# Grove_4-Digit_Display_V1_0.net
KiCad netlist of a schematic drawn in EAGLE
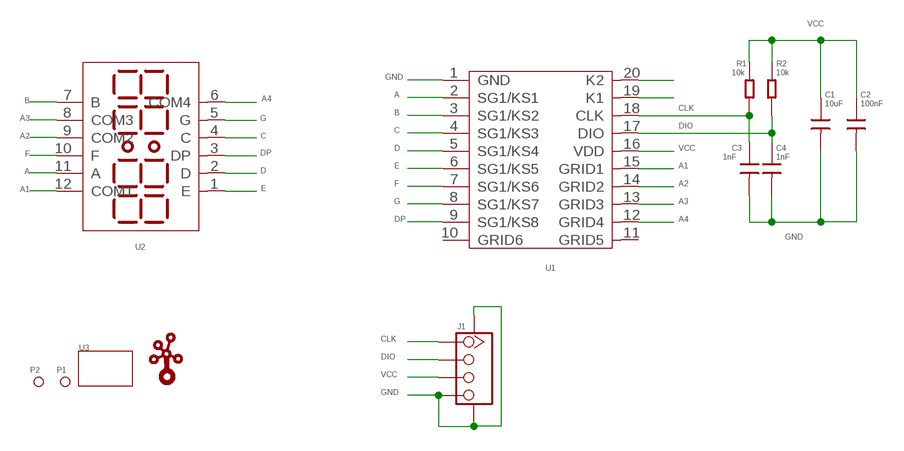
[diagram p0: schematic, sheet 1]

(export (version "E")
  (design (tool "Eeschema 10.0.6"))
  (components
    (comp (ref "C1")
      (value "10uF")
      (footprint "eagle-import:0603")
      (libsource (lib "eagle-import") (part "C-0603"))
    )
    (comp (ref "C2")
      (value "100nF")
      (footprint "eagle-import:0603")
      (libsource (lib "eagle-import") (part "C-0603"))
    )
    (comp (ref "C3")
      (value "1nF")
      (footprint "eagle-import:0603")
      (libsource (lib "eagle-import") (part "C-0603"))
    )
    (comp (ref "C4")
      (value "1nF")
      (footprint "eagle-import:0603")
      (libsource (lib "eagle-import") (part "C-0603"))
    )
    (comp (ref "J1")
      (value "TWIG-4P-2.0-SMD-FEMALE-REINFORCE'90D'")
      (footprint "eagle-import:4P-SMD-2.0-90D")
      (libsource (lib "eagle-import") (part "TWIG-4P-2.0-SMD-FEMALE-REINFORCE'90D'"))
    )
    (comp (ref "P1")
      (value "PAD-MARK")
      (footprint "eagle-import:ROUND-MARK-0.635")
      (libsource (lib "eagle-import") (part "PAD-MARK"))
    )
    (comp (ref "P2")
      (value "PAD-MARK")
      (footprint "eagle-import:ROUND-MARK-0.635")
      (libsource (lib "eagle-import") (part "PAD-MARK"))
    )
    (comp (ref "R1")
      (value "10k")
      (footprint "eagle-import:0603")
      (libsource (lib "eagle-import") (part "R-0603"))
    )
    (comp (ref "R2")
      (value "10k")
      (footprint "eagle-import:0603")
      (libsource (lib "eagle-import") (part "R-0603"))
    )
    (comp (ref "U$1")
      (value "LOGO-TWIGTWIGLOGO_SMALL")
      (footprint "eagle-import:TWIGLOGO_SMALL")
      (libsource (lib "eagle-import") (part "LOGO-TWIGTWIGLOGO_SMALL"))
    )
    (comp (ref "U1")
      (value "TM1637")
      (footprint "eagle-import:SOP20-10.45")
      (libsource (lib "eagle-import") (part "TM1637"))
    )
    (comp (ref "U2")
      (value "LED-4-BETY-7-SEG")
      (footprint "eagle-import:7-4-BYTE-SEG-2.54-30X14X7.3H")
      (libsource (lib "eagle-import") (part "LED-4-BETY-7-SEG"))
    )
    (comp (ref "U3")
      (value "TWIG-2U")
      (footprint "eagle-import:2U-DIM-W_-DRILL")
      (libsource (lib "eagle-import") (part "TWIG-2U"))
    )
  )
  (nets
    (net (code "1") (name "/A") (class "Default")
      (node (ref "U1") (pin "2") (pinfunction "SG1/KS1_2") (pintype "bidirectional"))
      (node (ref "U2") (pin "11") (pinfunction "A_11") (pintype "bidirectional"))
    )
    (net (code "2") (name "/A1") (class "Default")
      (node (ref "U1") (pin "15") (pinfunction "GRID1_15") (pintype "bidirectional"))
      (node (ref "U2") (pin "12") (pinfunction "COM1_12") (pintype "bidirectional"))
    )
    (net (code "3") (name "/A2") (class "Default")
      (node (ref "U1") (pin "14") (pinfunction "GRID2_14") (pintype "bidirectional"))
      (node (ref "U2") (pin "9") (pinfunction "COM2_9") (pintype "bidirectional"))
    )
    (net (code "4") (name "/A3") (class "Default")
      (node (ref "U1") (pin "13") (pinfunction "GRID3_13") (pintype "bidirectional"))
      (node (ref "U2") (pin "8") (pinfunction "COM3_8") (pintype "bidirectional"))
    )
    (net (code "5") (name "/A4") (class "Default")
      (node (ref "U1") (pin "12") (pinfunction "GRID4_12") (pintype "bidirectional"))
      (node (ref "U2") (pin "6") (pinfunction "COM4_6") (pintype "bidirectional"))
    )
    (net (code "6") (name "/B") (class "Default")
      (node (ref "U1") (pin "3") (pinfunction "SG1/KS2_3") (pintype "bidirectional"))
      (node (ref "U2") (pin "7") (pinfunction "B_7") (pintype "bidirectional"))
    )
    (net (code "7") (name "/C") (class "Default")
      (node (ref "U1") (pin "4") (pinfunction "SG1/KS3_4") (pintype "bidirectional"))
      (node (ref "U2") (pin "4") (pinfunction "C_4") (pintype "bidirectional"))
    )
    (net (code "8") (name "/CLK") (class "Default")
      (node (ref "C3") (pin "1") (pinfunction "1_1") (pintype "passive"))
      (node (ref "J1") (pin "1") (pinfunction "1_1") (pintype "bidirectional"))
      (node (ref "R1") (pin "2") (pinfunction "2_2") (pintype "passive"))
      (node (ref "U1") (pin "18") (pinfunction "CLK_18") (pintype "bidirectional"))
    )
    (net (code "9") (name "/D") (class "Default")
      (node (ref "U1") (pin "5") (pinfunction "SG1/KS4_5") (pintype "bidirectional"))
      (node (ref "U2") (pin "2") (pinfunction "D_2") (pintype "bidirectional"))
    )
    (net (code "10") (name "/DIO") (class "Default")
      (node (ref "C4") (pin "1") (pinfunction "1_1") (pintype "passive"))
      (node (ref "J1") (pin "2") (pinfunction "2_2") (pintype "bidirectional"))
      (node (ref "R2") (pin "2") (pinfunction "2_2") (pintype "passive"))
      (node (ref "U1") (pin "17") (pinfunction "DIO_17") (pintype "bidirectional"))
    )
    (net (code "11") (name "/DP") (class "Default")
      (node (ref "U1") (pin "9") (pinfunction "SG1/KS8_9") (pintype "bidirectional"))
      (node (ref "U2") (pin "3") (pinfunction "DP_3") (pintype "bidirectional"))
    )
    (net (code "12") (name "/E") (class "Default")
      (node (ref "U1") (pin "6") (pinfunction "SG1/KS5_6") (pintype "bidirectional"))
      (node (ref "U2") (pin "1") (pinfunction "E_1") (pintype "bidirectional"))
    )
    (net (code "13") (name "/F") (class "Default")
      (node (ref "U1") (pin "7") (pinfunction "SG1/KS6_7") (pintype "bidirectional"))
      (node (ref "U2") (pin "10") (pinfunction "F_10") (pintype "bidirectional"))
    )
    (net (code "14") (name "/G") (class "Default")
      (node (ref "U1") (pin "8") (pinfunction "SG1/KS7_8") (pintype "bidirectional"))
      (node (ref "U2") (pin "5") (pinfunction "G_5") (pintype "bidirectional"))
    )
    (net (code "15") (name "/GND") (class "Default")
      (node (ref "C1") (pin "2") (pinfunction "2_2") (pintype "passive"))
      (node (ref "C2") (pin "2") (pinfunction "2_2") (pintype "passive"))
      (node (ref "C3") (pin "2") (pinfunction "2_2") (pintype "passive"))
      (node (ref "C4") (pin "2") (pinfunction "2_2") (pintype "passive"))
      (node (ref "J1") (pin "4") (pinfunction "4_4") (pintype "bidirectional"))
      (node (ref "J1") (pin "SS1") (pinfunction "SS1_SS1") (pintype "bidirectional"))
      (node (ref "J1") (pin "SS2") (pinfunction "SS2_SS2") (pintype "bidirectional"))
      (node (ref "U1") (pin "1") (pinfunction "GND_1") (pintype "bidirectional"))
    )
    (net (code "16") (name "/VCC") (class "Default")
      (node (ref "C1") (pin "1") (pinfunction "1_1") (pintype "passive"))
      (node (ref "C2") (pin "1") (pinfunction "1_1") (pintype "passive"))
      (node (ref "J1") (pin "3") (pinfunction "3_3") (pintype "bidirectional"))
      (node (ref "R1") (pin "1") (pinfunction "1_1") (pintype "passive"))
      (node (ref "R2") (pin "1") (pinfunction "1_1") (pintype "passive"))
      (node (ref "U1") (pin "16") (pinfunction "VDD_16") (pintype "bidirectional"))
    )
    (net (code "17") (name "unconnected-(U1-GRID5-Pad11)") (class "Default")
      (node (ref "U1") (pin "11") (pinfunction "GRID5_11") (pintype "bidirectional"))
    )
    (net (code "18") (name "unconnected-(U1-GRID6-Pad10)") (class "Default")
      (node (ref "U1") (pin "10") (pinfunction "GRID6_10") (pintype "bidirectional"))
    )
    (net (code "19") (name "unconnected-(U1-K1-Pad19)") (class "Default")
      (node (ref "U1") (pin "19") (pinfunction "K1_19") (pintype "bidirectional"))
    )
    (net (code "20") (name "unconnected-(U1-K2-Pad20)") (class "Default")
      (node (ref "U1") (pin "20") (pinfunction "K2_20") (pintype "bidirectional"))
    )
  )
)
